# 1_sch.net
KiCad netlist of a schematic drawn in Altium Designer
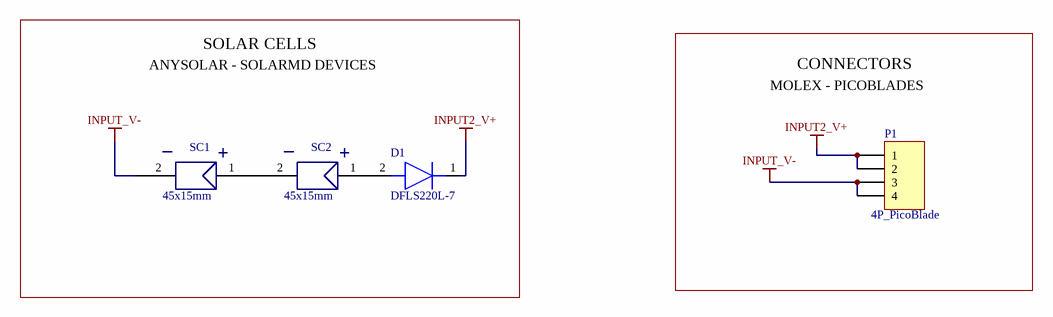
[diagram p0: 1_sch.schdoc]

(export (version "E")
  (design (tool "Eeschema 10.0.6"))
  (components
    (comp (ref "D1")
      (value "DFLS220L-7")
      (footprint "SamacSys:DFLS220L7")
      (description "Diode")
      (fields (field (name "MOUSER PART NUMBER") "621-DFLS220L-7"))
      (libsource (lib "*") (part "DFLS220L-7"))
    )
    (comp (ref "P1")
      (value "4P_PicoBlade")
      (footprint "HDR4 PicoBlade")
      (description "Header, 4-Pin")
      (fields
        (field (name "PARTNUMBER") "53398-0471")
        (field (name "MANUFACTURER") "Molex")
        (field (name "PUBLISHER") "Altium Limited")
      )
      (libsource (lib "schematics_library_legacy") (part "Header 4_PicoBlade"))
    )
    (comp (ref "SC1")
      (value "SC")
      (footprint "45x15mm_cell")
      (description "sm141k04lv")
      (fields (field (name "SIZE") "45x15mm"))
      (libsource (lib "schematics_library_legacy") (part "solar_cell_sm141k04lv"))
    )
    (comp (ref "SC2")
      (value "SC")
      (footprint "45x15mm_cell")
      (description "sm141k04lv")
      (fields (field (name "SIZE") "45x15mm"))
      (libsource (lib "schematics_library_legacy") (part "solar_cell_sm141k04lv"))
    )
  )
  (nets
    (net (code "1") (name "INPUT2_V+") (class "Default")
      (node (ref "D1") (pin "1") (pinfunction "K_1") (pintype "passive"))
      (node (ref "P1") (pin "1") (pinfunction "1_1") (pintype "passive"))
      (node (ref "P1") (pin "2") (pinfunction "2_2") (pintype "passive"))
    )
    (net (code "2") (name "INPUT_V-") (class "Default")
      (node (ref "P1") (pin "3") (pinfunction "3_3") (pintype "passive"))
      (node (ref "P1") (pin "4") (pinfunction "4_4") (pintype "passive"))
      (node (ref "SC1") (pin "2") (pinfunction "V-_2") (pintype "power_in"))
    )
    (net (code "3") (name "Net-(D1-A)") (class "Default")
      (node (ref "D1") (pin "2") (pinfunction "A_2") (pintype "passive"))
      (node (ref "SC2") (pin "1") (pinfunction "V+_1") (pintype "power_in"))
    )
    (net (code "4") (name "Net-(SC1-V+)") (class "Default")
      (node (ref "SC1") (pin "1") (pinfunction "V+_1") (pintype "power_in"))
      (node (ref "SC2") (pin "2") (pinfunction "V-_2") (pintype "power_in"))
    )
  )
)
